# COMUNICATE_CON.net
KiCad netlist of a schematic drawn in Altium Designer
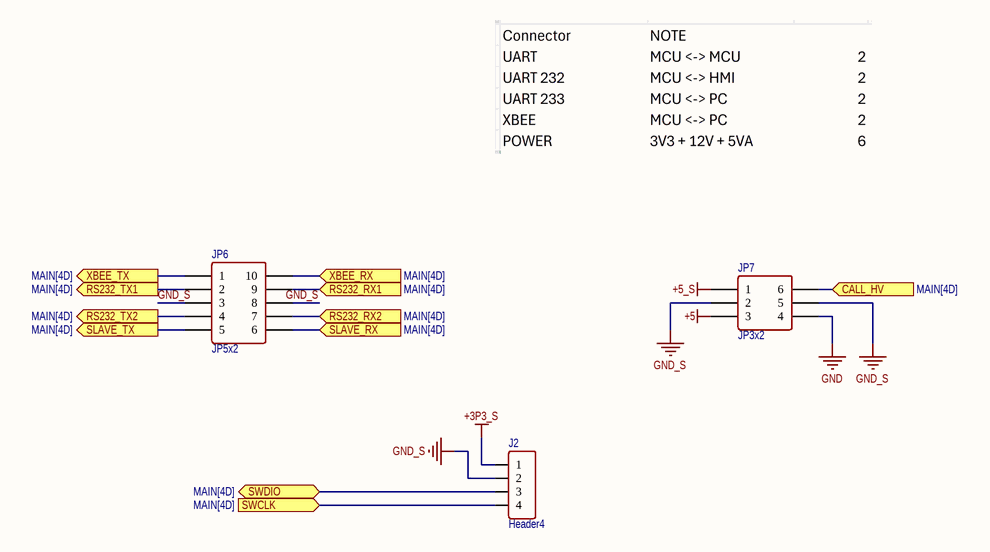
[diagram p0: COMUNICATE_CON.SchDoc]

(export (version "E")
  (design (tool "Eeschema 10.0.6"))
  (components
    (comp (ref "J2")
      (value "Header4")
      (footprint "XH2.54-4-DIP")
      (description "Connector 4")
      (fields
        (field (name "MANUFACTURER") "Würth Elektronik eiSos GmbH")
        (field (name "PARTNO") "613002143121")
        (field (name "CREATED BY") "Karrer Zheng")
      )
      (libsource (lib "Library") (part "Header4"))
    )
    (comp (ref "JP6")
      (value "JP5x2")
      (footprint "JP5-D2T")
      (description "WR-PHD 2.54 mm Dual Socket Header")
      (fields
        (field (name "MANUFACTURER") "Würth Elektronik eiSos GmbH")
        (field (name "PARTNO") "61301021821")
        (field (name "CREATED BY") "Karrer Zheng")
      )
      (libsource (lib "Library") (part "JP5x2"))
    )
    (comp (ref "JP7")
      (value "JP3x2")
      (footprint "JP3-C2T")
      (description "5-534206-3")
      (fields
        (field (name "MANUFACTURER") "Würth Elektronik eiSos GmbH")
        (field (name "PARTNO") "61300621821")
        (field (name "CREATED BY") "Karrer Zheng")
      )
      (libsource (lib "Library") (part "JP3x2"))
    )
  )
  (nets
    (net (code "1") (name "+3P3_S") (class "Default")
      (node (ref "J2") (pin "1") (pinfunction "1_1") (pintype "passive"))
    )
    (net (code "2") (name "+5") (class "Default")
      (node (ref "JP7") (pin "3") (pinfunction "3_3") (pintype "passive"))
    )
    (net (code "3") (name "+5_S") (class "Default")
      (node (ref "JP7") (pin "1") (pinfunction "1_1") (pintype "passive"))
    )
    (net (code "4") (name "/CALL_HV") (class "Default")
      (node (ref "JP7") (pin "6") (pinfunction "6_6") (pintype "passive"))
    )
    (net (code "5") (name "/RS232_RX1") (class "Default")
      (node (ref "JP6") (pin "9") (pinfunction "9_9") (pintype "passive"))
    )
    (net (code "6") (name "/RS232_RX2") (class "Default")
      (node (ref "JP6") (pin "7") (pinfunction "7_7") (pintype "passive"))
    )
    (net (code "7") (name "/RS232_TX1") (class "Default")
      (node (ref "JP6") (pin "2") (pinfunction "2_2") (pintype "passive"))
    )
    (net (code "8") (name "/RS232_TX2") (class "Default")
      (node (ref "JP6") (pin "4") (pinfunction "4_4") (pintype "passive"))
    )
    (net (code "9") (name "/SLAVE_RX") (class "Default")
      (node (ref "JP6") (pin "6") (pinfunction "6_6") (pintype "passive"))
    )
    (net (code "10") (name "/SLAVE_TX") (class "Default")
      (node (ref "JP6") (pin "5") (pinfunction "5_5") (pintype "passive"))
    )
    (net (code "11") (name "/SWCLK") (class "Default")
      (node (ref "J2") (pin "4") (pinfunction "4_4") (pintype "passive"))
    )
    (net (code "12") (name "/SWDIO") (class "Default")
      (node (ref "J2") (pin "3") (pinfunction "3_3") (pintype "passive"))
    )
    (net (code "13") (name "/XBEE_RX") (class "Default")
      (node (ref "JP6") (pin "10") (pinfunction "10_10") (pintype "passive"))
    )
    (net (code "14") (name "/XBEE_TX") (class "Default")
      (node (ref "JP6") (pin "1") (pinfunction "1_1") (pintype "passive"))
    )
    (net (code "15") (name "GND") (class "Default")
      (node (ref "JP7") (pin "4") (pinfunction "4_4") (pintype "passive"))
    )
    (net (code "16") (name "GND_S") (class "Default")
      (node (ref "J2") (pin "2") (pinfunction "2_2") (pintype "passive"))
      (node (ref "JP6") (pin "3") (pinfunction "3_3") (pintype "passive"))
      (node (ref "JP6") (pin "8") (pinfunction "8_8") (pintype "passive"))
      (node (ref "JP7") (pin "2") (pinfunction "2_2") (pintype "passive"))
      (node (ref "JP7") (pin "5") (pinfunction "5_5") (pintype "passive"))
    )
  )
)
